# PulseFit-Mini.net
KiCad netlist of a schematic drawn in EAGLE
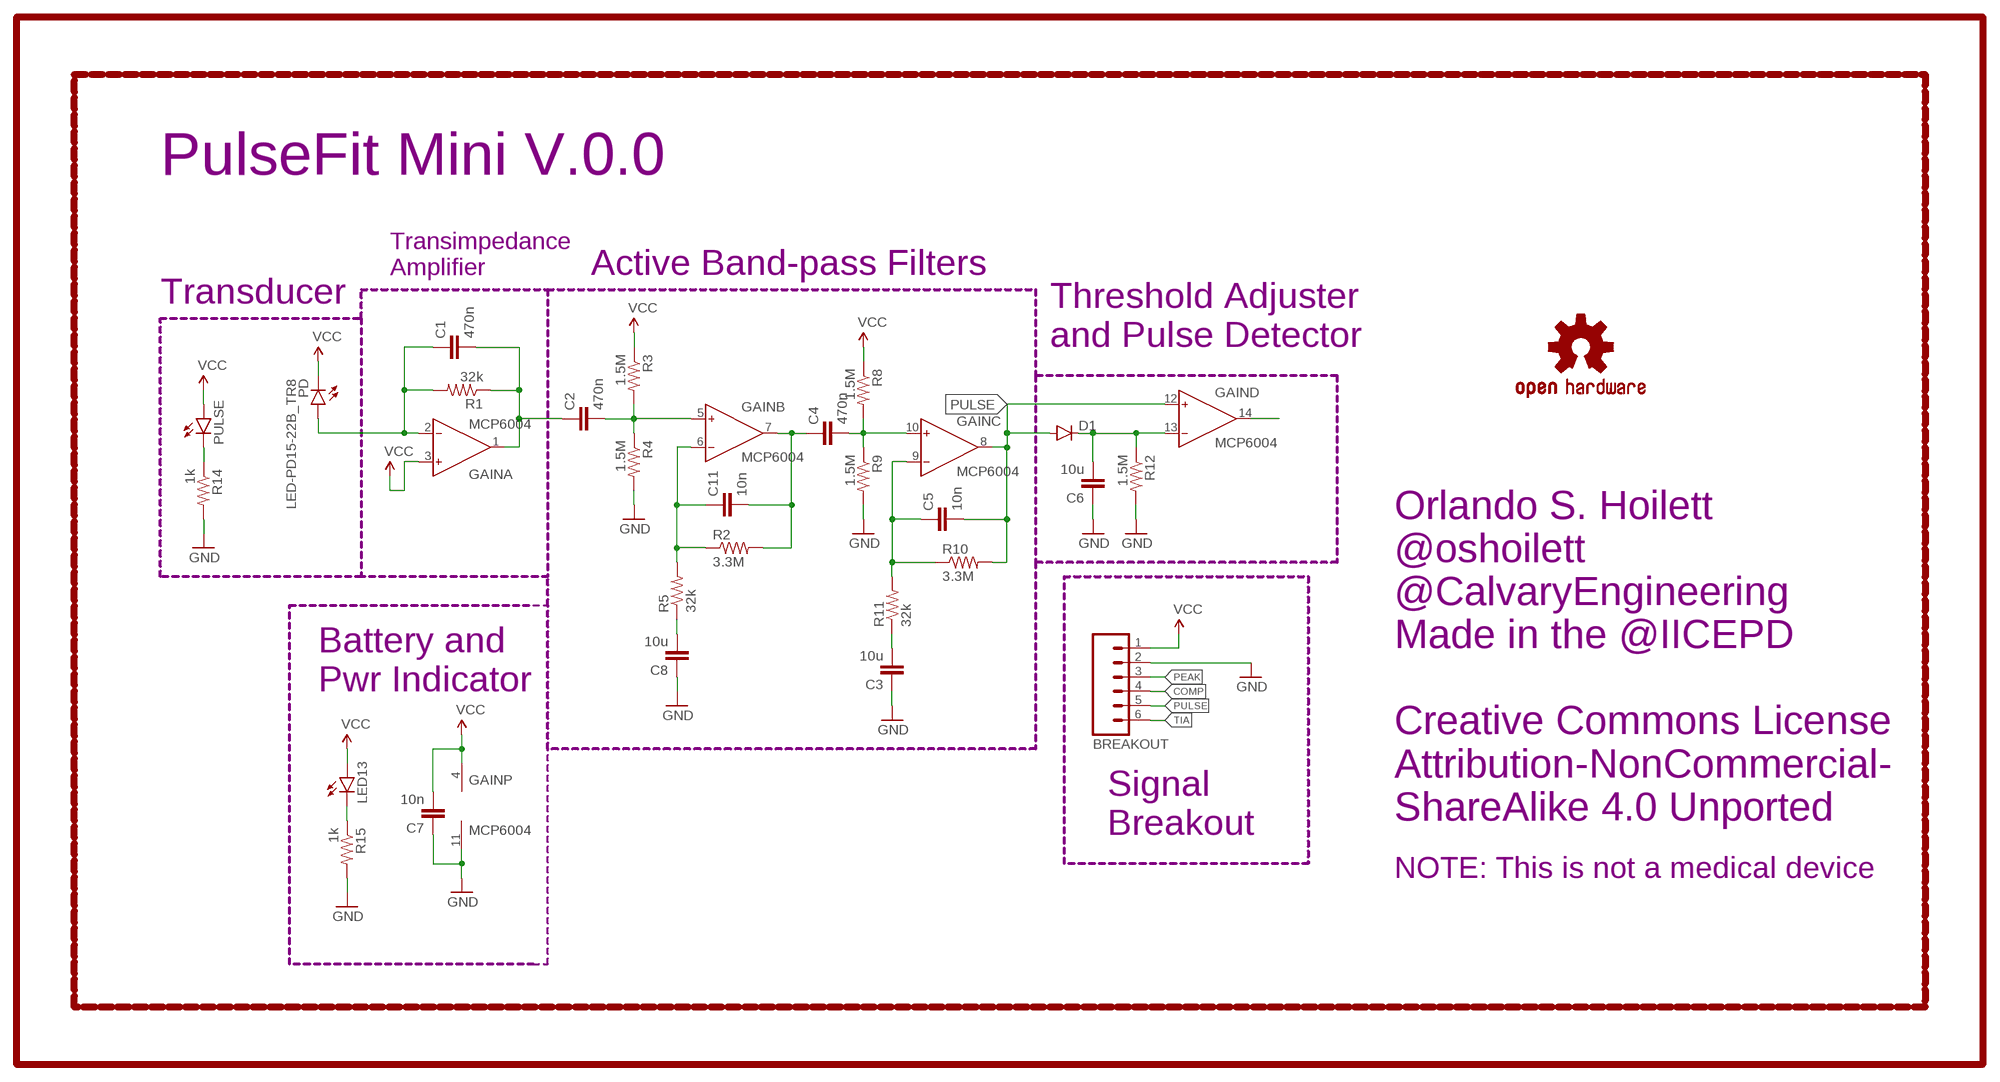
[diagram p0: schematic, sheet 1]

(export (version "E")
  (design (tool "Eeschema 10.0.6"))
  (components
    (comp (ref "BREAKOUT")
      (value "M06NO_SILK_FEMALE_PTH")
      (footprint "eagle-import:1X06_NO_SILK")
      (libsource (lib "eagle-import") (part "M06NO_SILK_FEMALE_PTH"))
    )
    (comp (ref "C1")
      (value "470n")
      (footprint "eagle-import:C0402")
      (libsource (lib "eagle-import") (part "C-EUC0402"))
    )
    (comp (ref "C2")
      (value "470n")
      (footprint "eagle-import:C0402")
      (libsource (lib "eagle-import") (part "C-EUC0402"))
    )
    (comp (ref "C3")
      (value "10u")
      (footprint "eagle-import:C0805")
      (libsource (lib "eagle-import") (part "C-EUC0805"))
    )
    (comp (ref "C4")
      (value "470n")
      (footprint "eagle-import:C0402")
      (libsource (lib "eagle-import") (part "C-EUC0402"))
    )
    (comp (ref "C5")
      (value "10n")
      (footprint "eagle-import:C0402")
      (libsource (lib "eagle-import") (part "C-EUC0402"))
    )
    (comp (ref "C6")
      (value "10u")
      (footprint "eagle-import:C0805")
      (libsource (lib "eagle-import") (part "C-EUC0805"))
    )
    (comp (ref "C7")
      (value "10n")
      (footprint "eagle-import:C0402")
      (libsource (lib "eagle-import") (part "C-EUC0402"))
    )
    (comp (ref "C8")
      (value "10u")
      (footprint "eagle-import:C0805")
      (libsource (lib "eagle-import") (part "C-EUC0805"))
    )
    (comp (ref "C11")
      (value "10n")
      (footprint "eagle-import:C0402")
      (libsource (lib "eagle-import") (part "C-EUC0402"))
    )
    (comp (ref "D1")
      (value "250mA/100V")
      (footprint "eagle-import:SOD-323")
      (libsource (lib "eagle-import") (part "DIODEBAS16"))
    )
    (comp (ref "GAIN")
      (value "MCP6004")
      (footprint "eagle-import:TSSOP14")
      (fields (field (name "MF") "ALTERA CORPORATION") (field (name "MPN") "AD8609ARUZ"))
      (libsource (lib "eagle-import") (part "AD8609RU"))
    )
    (comp (ref "LED13")
      (value "LED0603")
      (footprint "eagle-import:LED-0603")
      (libsource (lib "eagle-import") (part "LED0603"))
    )
    (comp (ref "LOGO1")
      (value "OSHW-LOGOS")
      (footprint "eagle-import:OSHW-LOGO-S")
      (libsource (lib "eagle-import") (part "OSHW-LOGOS"))
    )
    (comp (ref "PD")
      (value "LED-PD15-22B_TR8")
      (footprint "eagle-import:LED-PD15-22B_TR8")
      (libsource (lib "eagle-import") (part "LED-PD15-22B_TR8"))
    )
    (comp (ref "PULSE")
      (value "LED0603")
      (footprint "eagle-import:LED-0603")
      (libsource (lib "eagle-import") (part "LED0603"))
    )
    (comp (ref "R1")
      (value "32k")
      (footprint "eagle-import:R0402")
      (libsource (lib "eagle-import") (part "R-US_R0402"))
    )
    (comp (ref "R2")
      (value "3.3M")
      (footprint "eagle-import:R0402")
      (libsource (lib "eagle-import") (part "R-US_R0402"))
    )
    (comp (ref "R3")
      (value "1.5M")
      (footprint "eagle-import:R0402")
      (libsource (lib "eagle-import") (part "R-US_R0402"))
    )
    (comp (ref "R4")
      (value "1.5M")
      (footprint "eagle-import:R0402")
      (libsource (lib "eagle-import") (part "R-US_R0402"))
    )
    (comp (ref "R5")
      (value "32k")
      (footprint "eagle-import:R0402")
      (libsource (lib "eagle-import") (part "R-US_R0402"))
    )
    (comp (ref "R8")
      (value "1.5M")
      (footprint "eagle-import:R0402")
      (libsource (lib "eagle-import") (part "R-US_R0402"))
    )
    (comp (ref "R9")
      (value "1.5M")
      (footprint "eagle-import:R0402")
      (libsource (lib "eagle-import") (part "R-US_R0402"))
    )
    (comp (ref "R10")
      (value "3.3M")
      (footprint "eagle-import:R0402")
      (libsource (lib "eagle-import") (part "R-US_R0402"))
    )
    (comp (ref "R11")
      (value "32k")
      (footprint "eagle-import:R0402")
      (libsource (lib "eagle-import") (part "R-US_R0402"))
    )
    (comp (ref "R12")
      (value "1.5M")
      (footprint "eagle-import:R0402")
      (libsource (lib "eagle-import") (part "R-US_R0402"))
    )
    (comp (ref "R14")
      (value "1k")
      (footprint "eagle-import:R0402")
      (libsource (lib "eagle-import") (part "R-US_R0402"))
    )
    (comp (ref "R15")
      (value "1k")
      (footprint "eagle-import:R0402")
      (libsource (lib "eagle-import") (part "R-US_R0402"))
    )
  )
  (nets
    (net (code "1") (name "COMP") (class "Default")
      (node (ref "BREAKOUT") (pin "4") (pinfunction "4_4") (pintype "passive"))
      (node (ref "GAIN") (pin "14") (pinfunction "OUT_14") (pintype "output"))
    )
    (net (code "2") (name "GND") (class "Default")
      (node (ref "BREAKOUT") (pin "2") (pinfunction "2_2") (pintype "passive"))
      (node (ref "C3") (pin "1") (pinfunction "1_1") (pintype "passive"))
      (node (ref "C6") (pin "1") (pinfunction "1_1") (pintype "passive"))
      (node (ref "C7") (pin "1") (pinfunction "1_1") (pintype "passive"))
      (node (ref "C8") (pin "1") (pinfunction "1_1") (pintype "passive"))
      (node (ref "GAIN") (pin "11") (pinfunction "V-_11") (pintype "power_in"))
      (node (ref "R12") (pin "2") (pinfunction "2_2") (pintype "passive"))
      (node (ref "R14") (pin "2") (pinfunction "2_2") (pintype "passive"))
      (node (ref "R15") (pin "2") (pinfunction "2_2") (pintype "passive"))
      (node (ref "R4") (pin "2") (pinfunction "2_2") (pintype "passive"))
      (node (ref "R9") (pin "2") (pinfunction "2_2") (pintype "passive"))
    )
    (net (code "3") (name "Net-(C3-Pad2)") (class "Default")
      (node (ref "C3") (pin "2") (pinfunction "2_2") (pintype "passive"))
      (node (ref "R11") (pin "1") (pinfunction "1_1") (pintype "passive"))
    )
    (net (code "4") (name "Net-(C8-Pad2)") (class "Default")
      (node (ref "C8") (pin "2") (pinfunction "2_2") (pintype "passive"))
      (node (ref "R5") (pin "1") (pinfunction "1_1") (pintype "passive"))
    )
    (net (code "5") (name "Net-(GAINA-IN-)") (class "Default")
      (node (ref "C1") (pin "1") (pinfunction "1_1") (pintype "passive"))
      (node (ref "GAIN") (pin "2") (pinfunction "IN-_2") (pintype "input"))
      (node (ref "PD") (pin "A-1") (pinfunction "A_A-1") (pintype "passive"))
      (node (ref "PD") (pin "A-2") (pinfunction "A_A-2") (pintype "passive"))
      (node (ref "R1") (pin "2") (pinfunction "2_2") (pintype "passive"))
    )
    (net (code "6") (name "Net-(GAINB-IN+)") (class "Default")
      (node (ref "C2") (pin "2") (pinfunction "2_2") (pintype "passive"))
      (node (ref "GAIN") (pin "5") (pinfunction "IN+_5") (pintype "input"))
      (node (ref "R3") (pin "2") (pinfunction "2_2") (pintype "passive"))
      (node (ref "R4") (pin "1") (pinfunction "1_1") (pintype "passive"))
    )
    (net (code "7") (name "Net-(GAINB-IN-)") (class "Default")
      (node (ref "C11") (pin "1") (pinfunction "1_1") (pintype "passive"))
      (node (ref "GAIN") (pin "6") (pinfunction "IN-_6") (pintype "input"))
      (node (ref "R2") (pin "1") (pinfunction "1_1") (pintype "passive"))
      (node (ref "R5") (pin "2") (pinfunction "2_2") (pintype "passive"))
    )
    (net (code "8") (name "Net-(GAINB-OUT)") (class "Default")
      (node (ref "C11") (pin "2") (pinfunction "2_2") (pintype "passive"))
      (node (ref "C4") (pin "1") (pinfunction "1_1") (pintype "passive"))
      (node (ref "GAIN") (pin "7") (pinfunction "OUT_7") (pintype "output"))
      (node (ref "R2") (pin "2") (pinfunction "2_2") (pintype "passive"))
    )
    (net (code "9") (name "Net-(GAINC-IN+)") (class "Default")
      (node (ref "C4") (pin "2") (pinfunction "2_2") (pintype "passive"))
      (node (ref "GAIN") (pin "10") (pinfunction "IN+_10") (pintype "input"))
      (node (ref "R8") (pin "2") (pinfunction "2_2") (pintype "passive"))
      (node (ref "R9") (pin "1") (pinfunction "1_1") (pintype "passive"))
    )
    (net (code "10") (name "Net-(GAINC-IN-)") (class "Default")
      (node (ref "C5") (pin "1") (pinfunction "1_1") (pintype "passive"))
      (node (ref "GAIN") (pin "9") (pinfunction "IN-_9") (pintype "input"))
      (node (ref "R10") (pin "1") (pinfunction "1_1") (pintype "passive"))
      (node (ref "R11") (pin "2") (pinfunction "2_2") (pintype "passive"))
    )
    (net (code "11") (name "Net-(LED13-PadC)") (class "Default")
      (node (ref "LED13") (pin "C") (pinfunction "C_C") (pintype "passive"))
      (node (ref "R15") (pin "1") (pinfunction "1_1") (pintype "passive"))
    )
    (net (code "12") (name "Net-(PULSE-PadC)") (class "Default")
      (node (ref "PULSE") (pin "C") (pinfunction "C_C") (pintype "passive"))
      (node (ref "R14") (pin "1") (pinfunction "1_1") (pintype "passive"))
    )
    (net (code "13") (name "PEAK") (class "Default")
      (node (ref "BREAKOUT") (pin "3") (pinfunction "3_3") (pintype "passive"))
      (node (ref "C6") (pin "2") (pinfunction "2_2") (pintype "passive"))
      (node (ref "D1") (pin "C") (pinfunction "C_C") (pintype "passive"))
      (node (ref "GAIN") (pin "13") (pinfunction "IN-_13") (pintype "input"))
      (node (ref "R12") (pin "1") (pinfunction "1_1") (pintype "passive"))
    )
    (net (code "14") (name "PULSE") (class "Default")
      (node (ref "BREAKOUT") (pin "5") (pinfunction "5_5") (pintype "passive"))
      (node (ref "C5") (pin "2") (pinfunction "2_2") (pintype "passive"))
      (node (ref "D1") (pin "A") (pinfunction "A_A") (pintype "passive"))
      (node (ref "GAIN") (pin "12") (pinfunction "IN+_12") (pintype "input"))
      (node (ref "GAIN") (pin "8") (pinfunction "OUT_8") (pintype "output"))
      (node (ref "R10") (pin "2") (pinfunction "2_2") (pintype "passive"))
    )
    (net (code "15") (name "TIA") (class "Default")
      (node (ref "BREAKOUT") (pin "6") (pinfunction "6_6") (pintype "passive"))
      (node (ref "C1") (pin "2") (pinfunction "2_2") (pintype "passive"))
      (node (ref "C2") (pin "1") (pinfunction "1_1") (pintype "passive"))
      (node (ref "GAIN") (pin "1") (pinfunction "OUT_1") (pintype "output"))
      (node (ref "R1") (pin "1") (pinfunction "1_1") (pintype "passive"))
    )
    (net (code "16") (name "VCC") (class "Default")
      (node (ref "BREAKOUT") (pin "1") (pinfunction "1_1") (pintype "passive"))
      (node (ref "C7") (pin "2") (pinfunction "2_2") (pintype "passive"))
      (node (ref "GAIN") (pin "3") (pinfunction "IN+_3") (pintype "input"))
      (node (ref "GAIN") (pin "4") (pinfunction "V+_4") (pintype "power_in"))
      (node (ref "LED13") (pin "A") (pinfunction "A_A") (pintype "passive"))
      (node (ref "PD") (pin "C-1") (pinfunction "C_C-1") (pintype "passive"))
      (node (ref "PD") (pin "C-2") (pinfunction "C_C-2") (pintype "passive"))
      (node (ref "PULSE") (pin "A") (pinfunction "A_A") (pintype "passive"))
      (node (ref "R3") (pin "1") (pinfunction "1_1") (pintype "passive"))
      (node (ref "R8") (pin "1") (pinfunction "1_1") (pintype "passive"))
    )
  )
)
